# I2C_Devices.net
KiCad netlist of a schematic drawn in Altium Designer
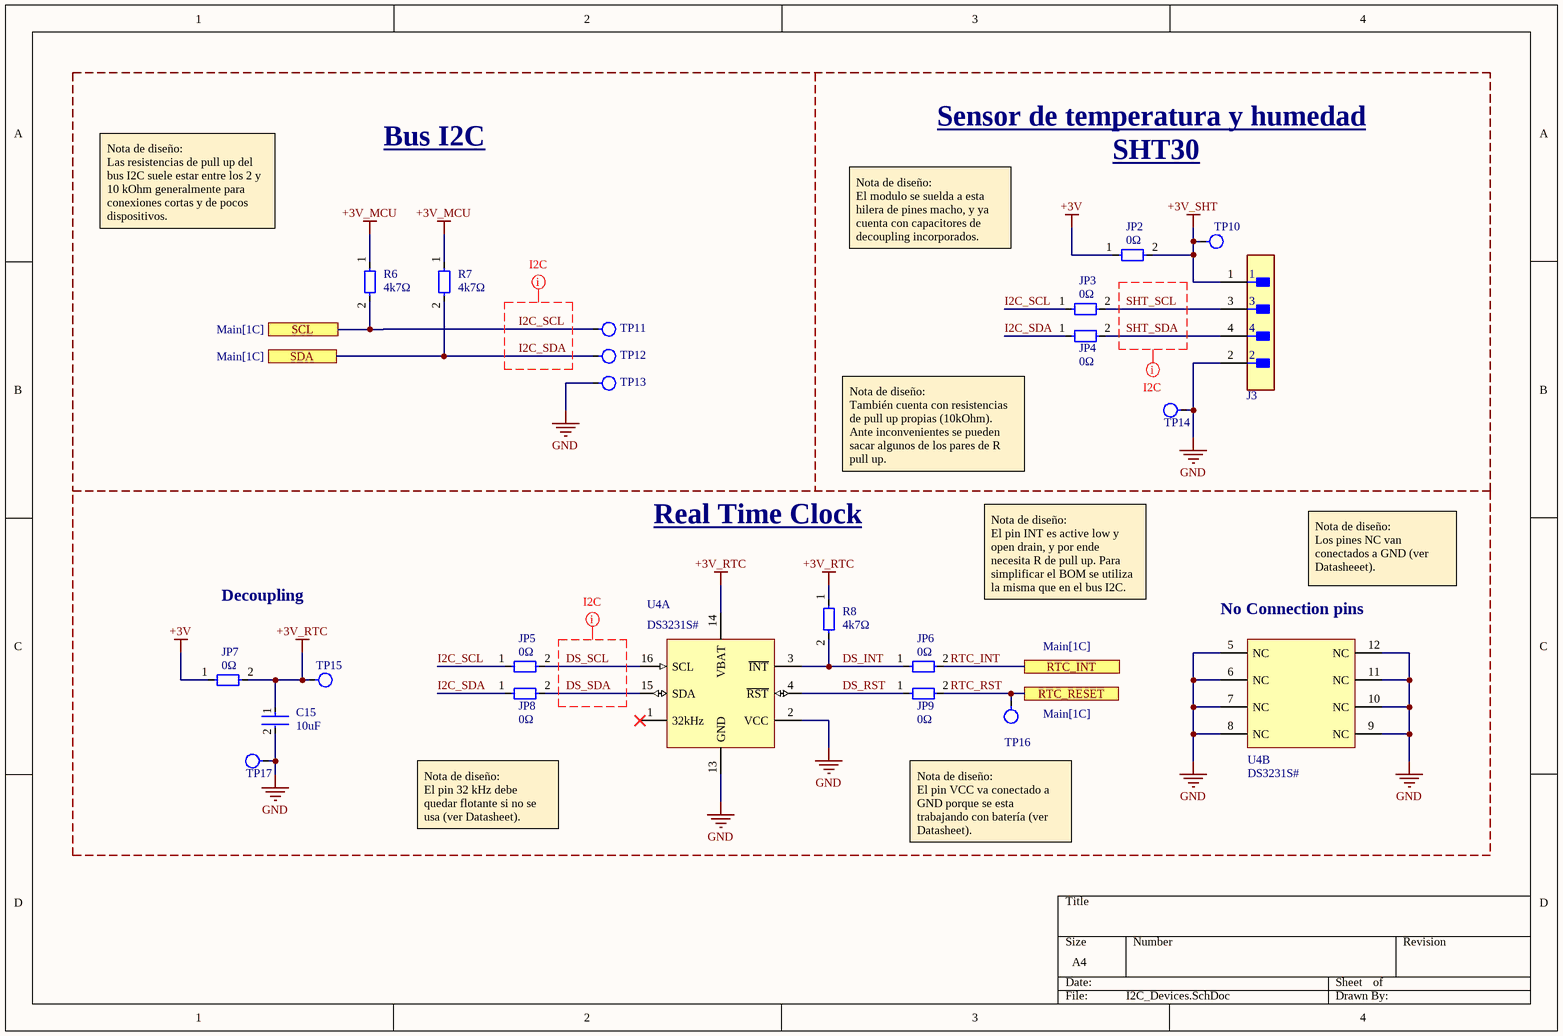
[diagram p0: I2C_Devices.SchDoc]

(export (version "E")
  (design (tool "Eeschema 10.0.6"))
  (components
    (comp (ref "C15")
      (value "10uF")
      (footprint "CAP_0603")
      (description "Cap 10  uF 10V X7R 0603")
      (fields (field (name "CAPACITANCE") "10uF") (field (name "TOLERANCE") "10%"))
      (libsource (lib "Passive_Components") (part "Generic C"))
    )
    (comp (ref "J3")
      (value "HTSW-104-07-G-S")
      (footprint "FP-HTSW-104-07-G-S-MFG")
      (description "CONN HEADER VERT 4POS 2.54MM. Versión alterna.")
      (libsource (lib "Connectors") (part "CMP-02766-001776_ALT"))
    )
    (comp (ref "JP2")
      (value "0Ω")
      (footprint "RES_0R_0603")
      (description "Simbolo de jumper genérico")
      (fields (field (name "Comment") "Generic JP"))
      (libsource (lib "Passive_Components") (part "Generic JP"))
    )
    (comp (ref "JP3")
      (value "0Ω")
      (footprint "RES_0R_0603")
      (description "Simbolo de jumper genérico")
      (fields (field (name "Comment") "Generic JP"))
      (libsource (lib "Passive_Components") (part "Generic JP"))
    )
    (comp (ref "JP4")
      (value "0Ω")
      (footprint "RES_0R_0603")
      (description "Simbolo de jumper genérico")
      (fields (field (name "Comment") "Generic JP"))
      (libsource (lib "Passive_Components") (part "Generic JP"))
    )
    (comp (ref "JP5")
      (value "0Ω")
      (footprint "RES_0R_0603")
      (description "Simbolo de jumper genérico")
      (fields (field (name "Comment") "Generic JP"))
      (libsource (lib "Passive_Components") (part "Generic JP"))
    )
    (comp (ref "JP6")
      (value "0Ω")
      (footprint "RES_0R_0603")
      (description "Simbolo de jumper genérico")
      (fields (field (name "Comment") "Generic JP"))
      (libsource (lib "Passive_Components") (part "Generic JP"))
    )
    (comp (ref "JP7")
      (value "0Ω")
      (footprint "RES_0R_0603")
      (description "Simbolo de jumper genérico")
      (fields (field (name "Comment") "Generic JP"))
      (libsource (lib "Passive_Components") (part "Generic JP"))
    )
    (comp (ref "JP8")
      (value "0Ω")
      (footprint "RES_0R_0603")
      (description "Simbolo de jumper genérico")
      (fields (field (name "Comment") "Generic JP"))
      (libsource (lib "Passive_Components") (part "Generic JP"))
    )
    (comp (ref "JP9")
      (value "0Ω")
      (footprint "RES_0R_0603")
      (description "Simbolo de jumper genérico")
      (fields (field (name "Comment") "Generic JP"))
      (libsource (lib "Passive_Components") (part "Generic JP"))
    )
    (comp (ref "R6")
      (value "4k7Ω")
      (footprint "RES_0603")
      (description "RES  4k7 1% 0603")
      (fields (field (name "Comment") "4k7"))
      (libsource (lib "Passive_Components") (part "Generic R"))
    )
    (comp (ref "R7")
      (value "4k7Ω")
      (footprint "RES_0603")
      (description "RES  4k7 1% 0603")
      (fields (field (name "Comment") "4k7"))
      (libsource (lib "Passive_Components") (part "Generic R"))
    )
    (comp (ref "R8")
      (value "4k7Ω")
      (footprint "RES_0603")
      (description "RES  4k7 1% 0603")
      (fields (field (name "Comment") "4k7"))
      (libsource (lib "Passive_Components") (part "Generic R"))
    )
    (comp (ref "TP10")
      (value "Testpoint SMD")
      (footprint "Testpoint_SMD")
      (description "Testpoint SMD de 1mm de diametro.")
      (libsource (lib "Connectors") (part "Testpoint_SMD"))
    )
    (comp (ref "TP11")
      (value "Testpoint SMD")
      (footprint "Testpoint_SMD")
      (description "Testpoint SMD de 1mm de diametro.")
      (libsource (lib "Connectors") (part "Testpoint_SMD"))
    )
    (comp (ref "TP12")
      (value "Testpoint SMD")
      (footprint "Testpoint_SMD")
      (description "Testpoint SMD de 1mm de diametro.")
      (libsource (lib "Connectors") (part "Testpoint_SMD"))
    )
    (comp (ref "TP13")
      (value "Testpoint SMD")
      (footprint "Testpoint_SMD")
      (description "Testpoint SMD de 1mm de diametro.")
      (libsource (lib "Connectors") (part "Testpoint_SMD"))
    )
    (comp (ref "TP14")
      (value "Testpoint SMD")
      (footprint "Testpoint_SMD")
      (description "Testpoint SMD de 1mm de diametro.")
      (libsource (lib "Connectors") (part "Testpoint_SMD"))
    )
    (comp (ref "TP15")
      (value "Testpoint SMD")
      (footprint "Testpoint_SMD")
      (description "Testpoint SMD de 1mm de diametro.")
      (libsource (lib "Connectors") (part "Testpoint_SMD"))
    )
    (comp (ref "TP16")
      (value "Testpoint SMD")
      (footprint "Testpoint_SMD")
      (description "Testpoint SMD de 1mm de diametro.")
      (libsource (lib "Connectors") (part "Testpoint_SMD"))
    )
    (comp (ref "TP17")
      (value "Testpoint SMD")
      (footprint "Testpoint_SMD")
      (description "Testpoint SMD de 1mm de diametro.")
      (libsource (lib "Connectors") (part "Testpoint_SMD"))
    )
    (comp (ref "U4")
      (value "DS3231S#")
      (footprint "SOIC_16_M")
      (description "IC RTC CLK/CALENDAR I2C 16SOIC. Symbol used with battery as the main supply voltage.")
      (libsource (lib "Real_Time_Clocks") (part "DS3231S# for battery use"))
    )
  )
  (nets
    (net (code "1") (name "+3V") (class "Default")
      (node (ref "JP2") (pin "1") (pinfunction "1_1") (pintype "passive"))
      (node (ref "JP7") (pin "1") (pinfunction "1_1") (pintype "passive"))
    )
    (net (code "2") (name "+3V_MCU") (class "Default")
      (node (ref "R6") (pin "1") (pinfunction "1_1") (pintype "passive"))
      (node (ref "R7") (pin "1") (pinfunction "1_1") (pintype "passive"))
    )
    (net (code "3") (name "+3V_RTC") (class "Default")
      (node (ref "C15") (pin "1") (pinfunction "1_1") (pintype "passive"))
      (node (ref "JP7") (pin "2") (pinfunction "2_2") (pintype "passive"))
      (node (ref "R8") (pin "1") (pinfunction "1_1") (pintype "passive"))
      (node (ref "TP15") (pin "1") (pinfunction "1_1") (pintype "passive"))
      (node (ref "U4") (pin "14") (pinfunction "VBAT_14") (pintype "power_in"))
    )
    (net (code "4") (name "+3V_SHT") (class "Default")
      (node (ref "J3") (pin "1") (pinfunction "1_1") (pintype "passive"))
      (node (ref "JP2") (pin "2") (pinfunction "2_2") (pintype "passive"))
      (node (ref "TP10") (pin "1") (pinfunction "1_1") (pintype "passive"))
    )
    (net (code "5") (name "/DS_INT") (class "Default")
      (node (ref "JP6") (pin "1") (pinfunction "1_1") (pintype "passive"))
      (node (ref "R8") (pin "2") (pinfunction "2_2") (pintype "passive"))
      (node (ref "U4") (pin "3") (pinfunction "INT_3") (pintype "open_collector"))
    )
    (net (code "6") (name "/DS_RST") (class "Default")
      (node (ref "JP9") (pin "1") (pinfunction "1_1") (pintype "passive"))
      (node (ref "U4") (pin "4") (pinfunction "RST_4") (pintype "bidirectional"))
    )
    (net (code "7") (name "/DS_SCL") (class "Default")
      (node (ref "JP5") (pin "2") (pinfunction "2_2") (pintype "passive"))
      (node (ref "U4") (pin "16") (pinfunction "SCL_16") (pintype "input"))
    )
    (net (code "8") (name "/DS_SDA") (class "Default")
      (node (ref "JP8") (pin "2") (pinfunction "2_2") (pintype "passive"))
      (node (ref "U4") (pin "15") (pinfunction "SDA_15") (pintype "bidirectional"))
    )
    (net (code "9") (name "/I2C_SCL") (class "Default")
      (node (ref "JP3") (pin "1") (pinfunction "1_1") (pintype "passive"))
      (node (ref "JP5") (pin "1") (pinfunction "1_1") (pintype "passive"))
      (node (ref "R6") (pin "2") (pinfunction "2_2") (pintype "passive"))
      (node (ref "TP11") (pin "1") (pinfunction "1_1") (pintype "passive"))
    )
    (net (code "10") (name "/I2C_SDA") (class "Default")
      (node (ref "JP4") (pin "1") (pinfunction "1_1") (pintype "passive"))
      (node (ref "JP8") (pin "1") (pinfunction "1_1") (pintype "passive"))
      (node (ref "R7") (pin "2") (pinfunction "2_2") (pintype "passive"))
      (node (ref "TP12") (pin "1") (pinfunction "1_1") (pintype "passive"))
    )
    (net (code "11") (name "/RTC_INT") (class "Default")
      (node (ref "JP6") (pin "2") (pinfunction "2_2") (pintype "passive"))
    )
    (net (code "12") (name "/RTC_RST") (class "Default")
      (node (ref "JP9") (pin "2") (pinfunction "2_2") (pintype "passive"))
      (node (ref "TP16") (pin "1") (pinfunction "1_1") (pintype "passive"))
    )
    (net (code "13") (name "/SHT_SCL") (class "Default")
      (node (ref "J3") (pin "3") (pinfunction "3_3") (pintype "passive"))
      (node (ref "JP3") (pin "2") (pinfunction "2_2") (pintype "passive"))
    )
    (net (code "14") (name "/SHT_SDA") (class "Default")
      (node (ref "J3") (pin "4") (pinfunction "4_4") (pintype "passive"))
      (node (ref "JP4") (pin "2") (pinfunction "2_2") (pintype "passive"))
    )
    (net (code "15") (name "GND") (class "Default")
      (node (ref "C15") (pin "2") (pinfunction "2_2") (pintype "passive"))
      (node (ref "J3") (pin "2") (pinfunction "2_2") (pintype "passive"))
      (node (ref "TP13") (pin "1") (pinfunction "1_1") (pintype "passive"))
      (node (ref "TP14") (pin "1") (pinfunction "1_1") (pintype "passive"))
      (node (ref "TP17") (pin "1") (pinfunction "1_1") (pintype "passive"))
      (node (ref "U4") (pin "10") (pinfunction "NC_10") (pintype "passive"))
      (node (ref "U4") (pin "11") (pinfunction "NC_11") (pintype "passive"))
      (node (ref "U4") (pin "12") (pinfunction "NC_12") (pintype "passive"))
      (node (ref "U4") (pin "13") (pinfunction "GND_13") (pintype "power_in"))
      (node (ref "U4") (pin "2") (pinfunction "VCC_2") (pintype "power_in"))
      (node (ref "U4") (pin "5") (pinfunction "NC_5") (pintype "passive"))
      (node (ref "U4") (pin "6") (pinfunction "NC_6") (pintype "passive"))
      (node (ref "U4") (pin "7") (pinfunction "NC_7") (pintype "passive"))
      (node (ref "U4") (pin "8") (pinfunction "NC_8") (pintype "passive"))
      (node (ref "U4") (pin "9") (pinfunction "NC_9") (pintype "passive"))
    )
    (net (code "16") (name "unconnected-(U4A-32kHz-Pad1)") (class "Default")
      (node (ref "U4") (pin "1") (pinfunction "32kHz_1") (pintype "open_collector+no_connect"))
    )
  )
)
